# attinydevboard.net
KiCad netlist of a schematic drawn in EAGLE
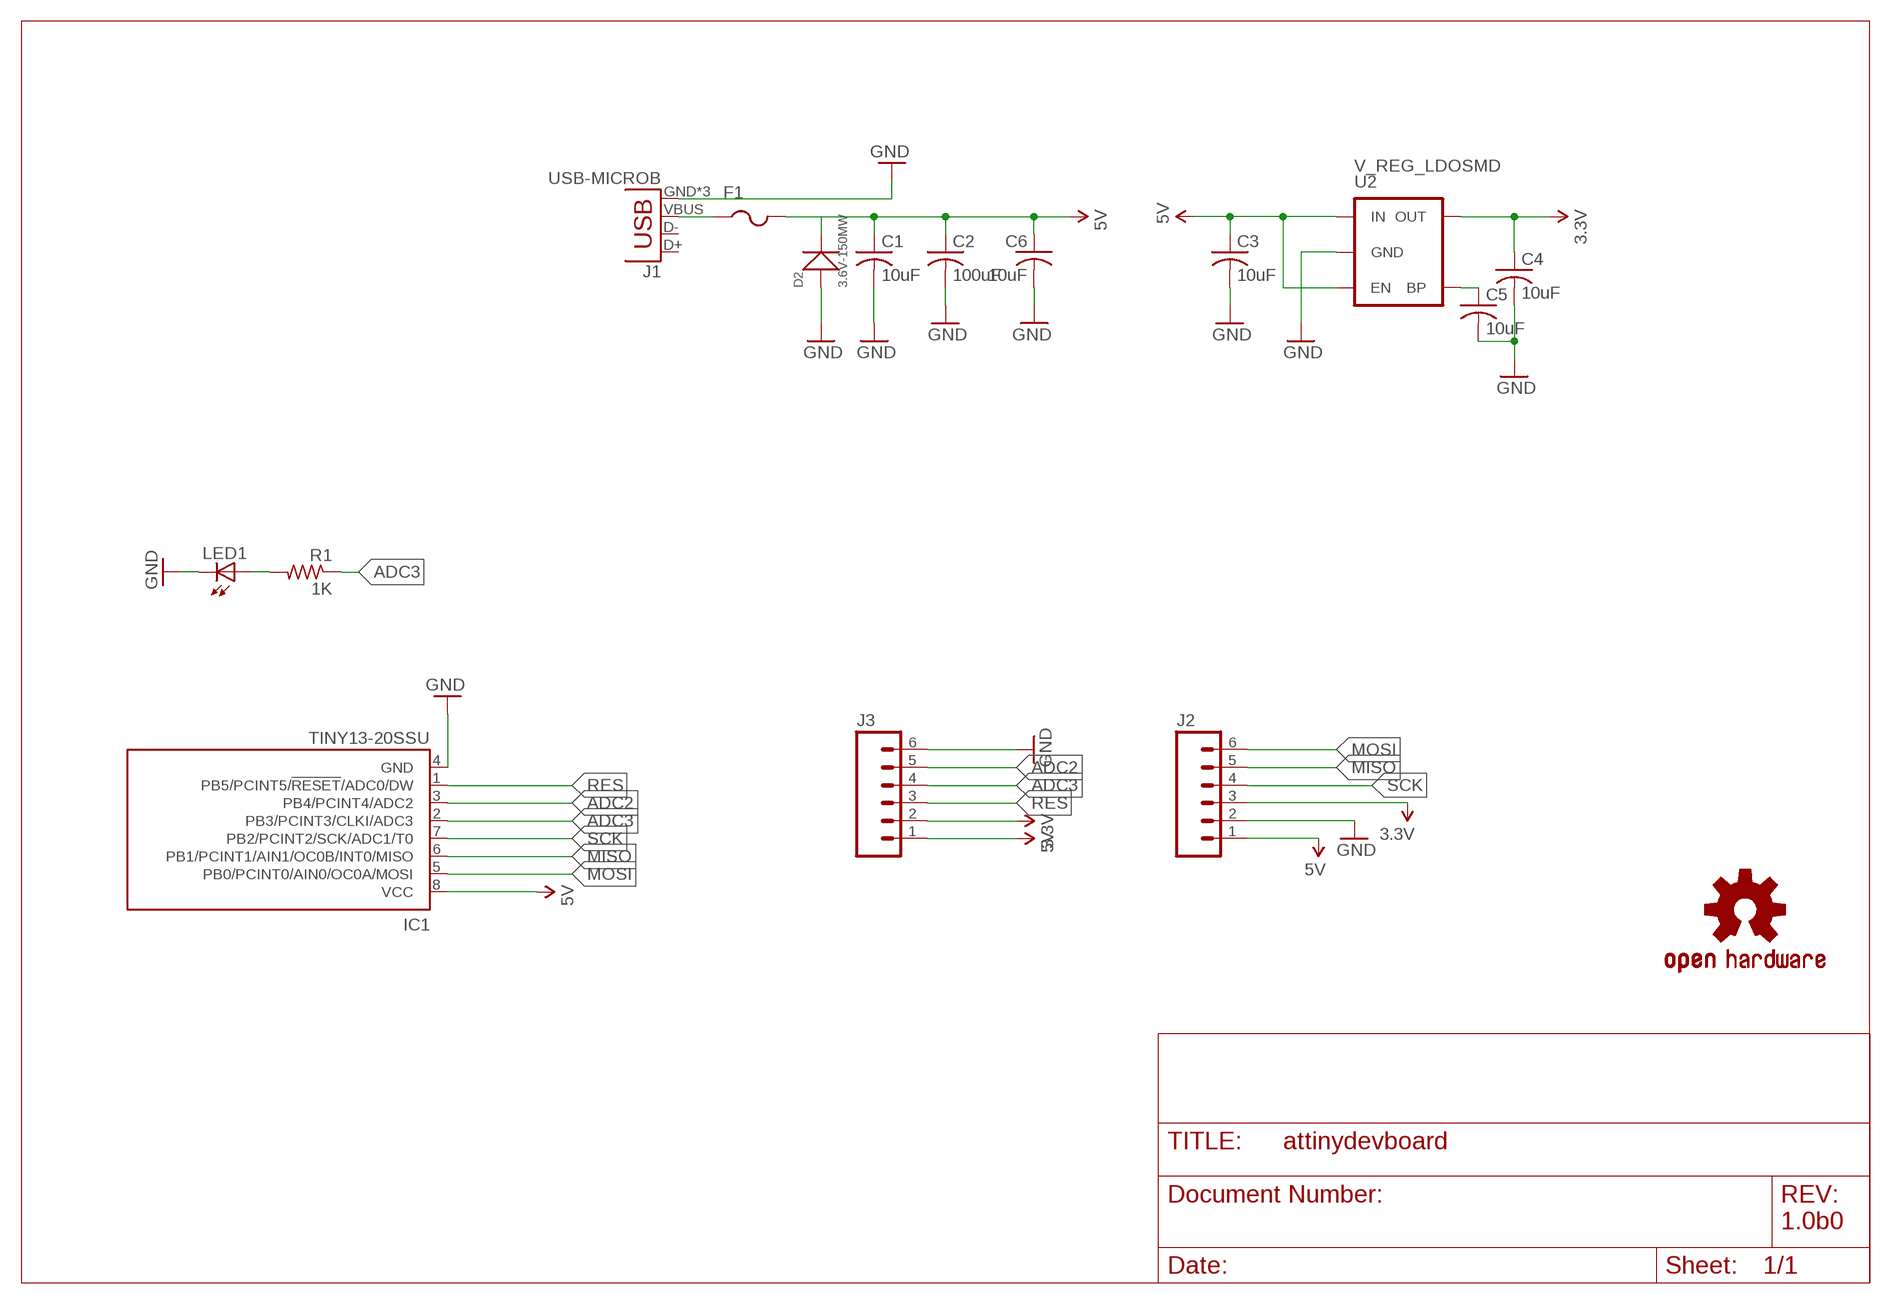
[diagram p0: schematic, sheet 1]

(export (version "E")
  (design (tool "Eeschema 10.0.6"))
  (components
    (comp (ref "C1")
      (value "10uF")
      (footprint "eagle-import:C0603")
      (libsource (lib "eagle-import") (part "C-USC0603"))
    )
    (comp (ref "C2")
      (value "100uF")
      (footprint "eagle-import:C0603")
      (libsource (lib "eagle-import") (part "C-USC0603"))
    )
    (comp (ref "C3")
      (value "10uF")
      (footprint "eagle-import:C0603")
      (libsource (lib "eagle-import") (part "C-USC0603"))
    )
    (comp (ref "C4")
      (value "10uF")
      (footprint "eagle-import:C0603")
      (libsource (lib "eagle-import") (part "C-USC0603"))
    )
    (comp (ref "C5")
      (value "10uF")
      (footprint "eagle-import:C0603")
      (libsource (lib "eagle-import") (part "C-USC0603"))
    )
    (comp (ref "C6")
      (value "10uF")
      (footprint "eagle-import:C0603")
      (libsource (lib "eagle-import") (part "C-USC0603"))
    )
    (comp (ref "D2")
      (value "3.6V-150MW")
      (footprint "eagle-import:SOD-523")
      (fields (field (name "MPN") "BZX584C3V6"))
      (libsource (lib "eagle-import") (part "SMD-DIODE-ZENER-3.6V-150MW(SOD-523)"))
    )
    (comp (ref "F1")
      (value "PTCFUSE-1206")
      (footprint "eagle-import:R1206")
      (libsource (lib "eagle-import") (part "PTCFUSE-1206"))
    )
    (comp (ref "IC1")
      (value "TINY13-20SSU")
      (footprint "eagle-import:8S1")
      (fields (field (name "MPN") "ATTINY13-20SSU"))
      (libsource (lib "eagle-import") (part "TINY13SSU-20"))
    )
    (comp (ref "J1")
      (value "USB-MICROB")
      (footprint "eagle-import:USB-MICROB")
      (libsource (lib "eagle-import") (part "USB-MICROB"))
    )
    (comp (ref "J2")
      (value "M06SIP")
      (footprint "eagle-import:1X06")
      (libsource (lib "eagle-import") (part "M06SIP"))
    )
    (comp (ref "J3")
      (value "M06SIP")
      (footprint "eagle-import:1X06")
      (libsource (lib "eagle-import") (part "M06SIP"))
    )
    (comp (ref "LED1")
      (value "LED0603")
      (footprint "eagle-import:LED-0603")
      (libsource (lib "eagle-import") (part "LED0603"))
    )
    (comp (ref "R1")
      (value "1K")
      (footprint "eagle-import:R0603")
      (libsource (lib "eagle-import") (part "R-US_R0603"))
    )
    (comp (ref "U$2")
      (value "OSHW-LOGOS")
      (footprint "eagle-import:OSHW-LOGO-S")
      (libsource (lib "eagle-import") (part "OSHW-LOGOS"))
    )
    (comp (ref "U2")
      (value "V_REG_LDOSMD")
      (footprint "eagle-import:SOT23-5")
      (libsource (lib "eagle-import") (part "V_REG_LDOSMD"))
    )
  )
  (nets
    (net (code "1") (name "3.3V") (class "Default")
      (node (ref "C4") (pin "1") (pinfunction "1_1") (pintype "passive"))
      (node (ref "J2") (pin "3") (pinfunction "3_3") (pintype "passive"))
      (node (ref "J3") (pin "2") (pinfunction "2_2") (pintype "passive"))
      (node (ref "U2") (pin "5") (pinfunction "OUT_5") (pintype "passive"))
    )
    (net (code "2") (name "5V") (class "Default")
      (node (ref "C1") (pin "1") (pinfunction "1_1") (pintype "passive"))
      (node (ref "C2") (pin "1") (pinfunction "1_1") (pintype "passive"))
      (node (ref "C3") (pin "1") (pinfunction "1_1") (pintype "passive"))
      (node (ref "C6") (pin "1") (pinfunction "1_1") (pintype "passive"))
      (node (ref "D2") (pin "-") (pinfunction "-_-") (pintype "passive"))
      (node (ref "F1") (pin "2") (pinfunction "2_2") (pintype "passive"))
      (node (ref "IC1") (pin "8") (pinfunction "VCC_8") (pintype "power_in"))
      (node (ref "J2") (pin "1") (pinfunction "1_1") (pintype "passive"))
      (node (ref "J3") (pin "1") (pinfunction "1_1") (pintype "passive"))
      (node (ref "U2") (pin "1") (pinfunction "IN_1") (pintype "input"))
      (node (ref "U2") (pin "3") (pinfunction "EN_3") (pintype "input"))
    )
    (net (code "3") (name "ADC2") (class "Default")
      (node (ref "IC1") (pin "3") (pinfunction "PB4/PCINT4/ADC2_3") (pintype "bidirectional"))
      (node (ref "J3") (pin "5") (pinfunction "5_5") (pintype "passive"))
    )
    (net (code "4") (name "ADC3") (class "Default")
      (node (ref "IC1") (pin "2") (pinfunction "PB3/PCINT3/CLKI/ADC3_2") (pintype "bidirectional"))
      (node (ref "J3") (pin "4") (pinfunction "4_4") (pintype "passive"))
      (node (ref "R1") (pin "1") (pinfunction "1_1") (pintype "passive"))
    )
    (net (code "5") (name "GND") (class "Default")
      (node (ref "C1") (pin "2") (pinfunction "2_2") (pintype "passive"))
      (node (ref "C2") (pin "2") (pinfunction "2_2") (pintype "passive"))
      (node (ref "C3") (pin "2") (pinfunction "2_2") (pintype "passive"))
      (node (ref "C4") (pin "2") (pinfunction "2_2") (pintype "passive"))
      (node (ref "C5") (pin "2") (pinfunction "2_2") (pintype "passive"))
      (node (ref "C6") (pin "2") (pinfunction "2_2") (pintype "passive"))
      (node (ref "D2") (pin "+") (pinfunction "+_+") (pintype "passive"))
      (node (ref "IC1") (pin "4") (pinfunction "GND_4") (pintype "power_in"))
      (node (ref "J1") (pin "GND") (pinfunction "GND_GND") (pintype "bidirectional"))
      (node (ref "J1") (pin "MT1") (pinfunction "GND_MT1") (pintype "bidirectional"))
      (node (ref "J1") (pin "MT2") (pinfunction "GND_MT2") (pintype "bidirectional"))
      (node (ref "J2") (pin "2") (pinfunction "2_2") (pintype "passive"))
      (node (ref "J3") (pin "6") (pinfunction "6_6") (pintype "passive"))
      (node (ref "LED1") (pin "C") (pinfunction "C_C") (pintype "passive"))
      (node (ref "U2") (pin "2") (pinfunction "GND_2") (pintype "input"))
    )
    (net (code "6") (name "MISO") (class "Default")
      (node (ref "IC1") (pin "6") (pinfunction "PB1/PCINT1/AIN1/OC0B/INT0/MISO_6") (pintype "bidirectional"))
      (node (ref "J2") (pin "5") (pinfunction "5_5") (pintype "passive"))
    )
    (net (code "7") (name "MOSI") (class "Default")
      (node (ref "IC1") (pin "5") (pinfunction "PB0/PCINT0/AIN0/OC0A/MOSI_5") (pintype "bidirectional"))
      (node (ref "J2") (pin "6") (pinfunction "6_6") (pintype "passive"))
    )
    (net (code "8") (name "Net-(F1-Pad1)") (class "Default")
      (node (ref "F1") (pin "1") (pinfunction "1_1") (pintype "passive"))
      (node (ref "J1") (pin "VBUS") (pinfunction "VBUS_VBUS") (pintype "bidirectional"))
    )
    (net (code "9") (name "Net-(LED1-PadA)") (class "Default")
      (node (ref "LED1") (pin "A") (pinfunction "A_A") (pintype "passive"))
      (node (ref "R1") (pin "2") (pinfunction "2_2") (pintype "passive"))
    )
    (net (code "10") (name "Net-(U2-BP)") (class "Default")
      (node (ref "C5") (pin "1") (pinfunction "1_1") (pintype "passive"))
      (node (ref "U2") (pin "4") (pinfunction "BP_4") (pintype "input"))
    )
    (net (code "11") (name "RES") (class "Default")
      (node (ref "IC1") (pin "1") (pinfunction "PB5/PCINT5/~{RESET}/ADC0/DW_1") (pintype "bidirectional"))
      (node (ref "J3") (pin "3") (pinfunction "3_3") (pintype "passive"))
    )
    (net (code "12") (name "SCK") (class "Default")
      (node (ref "IC1") (pin "7") (pinfunction "PB2/PCINT2/SCK/ADC1/T0_7") (pintype "bidirectional"))
      (node (ref "J2") (pin "4") (pinfunction "4_4") (pintype "passive"))
    )
    (net (code "13") (name "unconnected-(J1-PadD+)") (class "Default")
      (node (ref "J1") (pin "D+") (pinfunction "D+_D+") (pintype "bidirectional"))
    )
    (net (code "14") (name "unconnected-(J1-PadD-)") (class "Default")
      (node (ref "J1") (pin "D-") (pinfunction "D-_D-") (pintype "bidirectional"))
    )
  )
)
